# PotsDuino.net
KiCad netlist of a schematic drawn in Altium Designer
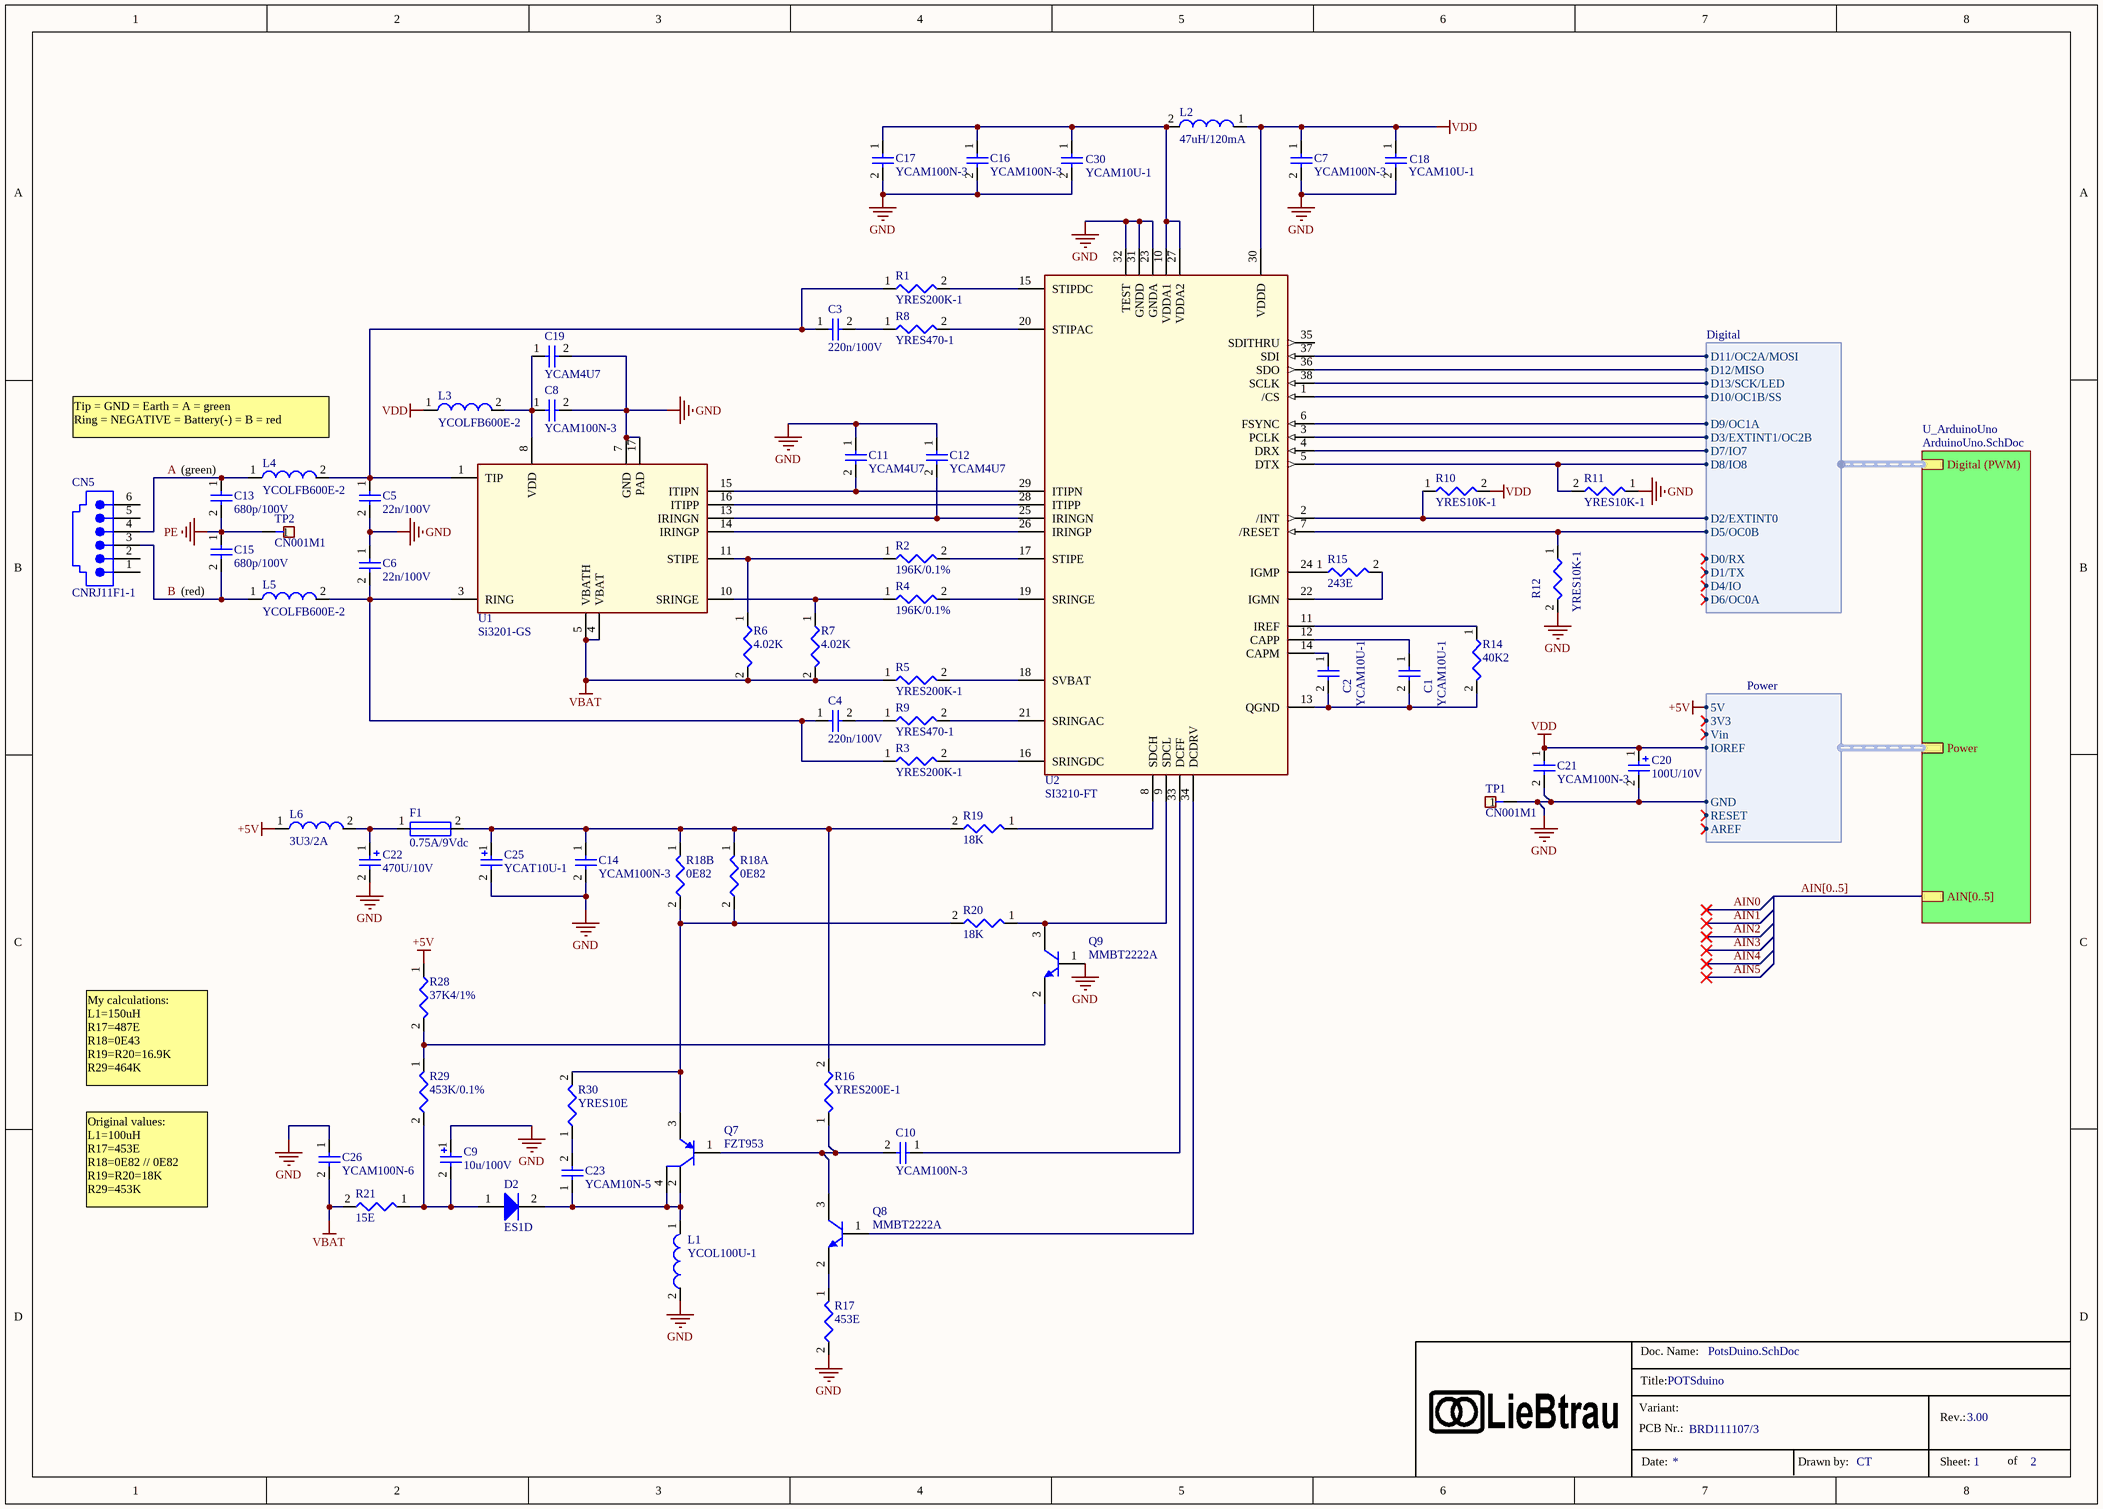
[diagram p0: PotsDuino.SchDoc]

(export (version "E")
  (design (tool "Eeschema 10.0.6"))
  (components
    (comp (ref "C1") (value "YCAM10U-1") (footprint "CA_0805") (libsource (lib "Testing") (part "CA_NONPOL")))
    (comp (ref "C2") (value "YCAM10U-1") (footprint "CA_0805") (libsource (lib "Testing") (part "CA_NONPOL")))
    (comp (ref "C3")
      (value "220n/100V")
      (footprint "CA_0805")
      (fields (field (name "PART NUMBER") "MCCA000493") (field (name "MANUFACTURER") "Multicomp"))
      (libsource (lib "Testing") (part "CA_NONPOL"))
    )
    (comp (ref "C4")
      (value "220n/100V")
      (footprint "CA_0805")
      (fields (field (name "PART NUMBER") "MCCA000493") (field (name "MANUFACTURER") "Multicomp"))
      (libsource (lib "Testing") (part "CA_NONPOL"))
    )
    (comp (ref "C5")
      (value "22n/100V")
      (footprint "CA_0603")
      (fields (field (name "PART NUMBER") "C0603C223K1RACTU") (field (name "MANUFACTURER") "Kemet"))
      (libsource (lib "Testing") (part "CA_NONPOL"))
    )
    (comp (ref "C6")
      (value "22n/100V")
      (footprint "CA_0603")
      (fields (field (name "PART NUMBER") "C0603C223K1RACTU") (field (name "MANUFACTURER") "Kemet"))
      (libsource (lib "Testing") (part "CA_NONPOL"))
    )
    (comp (ref "C7")
      (value "YCAM100N-3")
      (footprint "CA_0603")
      (libsource (lib "Testing") (part "CA_NONPOL"))
    )
    (comp (ref "C8")
      (value "YCAM100N-3")
      (footprint "CA_0603")
      (libsource (lib "Testing") (part "CA_NONPOL"))
    )
    (comp (ref "C9")
      (value "10u/100V")
      (footprint "CA_CANTHD63P25_H110_R")
      (fields (field (name "PART NUMBER") "100YXF10MEFC6.3X11") (field (name "MANUFACTURER") "Rubycon"))
      (libsource (lib "Testing") (part "CA_POL"))
    )
    (comp (ref "C10")
      (value "YCAM100N-3")
      (footprint "CA_0603")
      (libsource (lib "Testing") (part "CA_NONPOL"))
    )
    (comp (ref "C11") (value "YCAM4U7") (footprint "CA_1206") (libsource (lib "Testing") (part "CA_NONPOL")))
    (comp (ref "C12") (value "YCAM4U7") (footprint "CA_1206") (libsource (lib "Testing") (part "CA_NONPOL")))
    (comp (ref "C13")
      (value "680p/100V")
      (footprint "CA_0603")
      (fields (field (name "PART NUMBER") "C0603C681J1GACTU") (field (name "MANUFACTURER") "Kemet"))
      (libsource (lib "Testing") (part "CA_NONPOL"))
    )
    (comp (ref "C14")
      (value "YCAM100N-3")
      (footprint "CA_0603")
      (libsource (lib "Testing") (part "CA_NONPOL"))
    )
    (comp (ref "C15")
      (value "680p/100V")
      (footprint "CA_0603")
      (fields (field (name "PART NUMBER") "C0603C681J1GACTU") (field (name "MANUFACTURER") "Kemet"))
      (libsource (lib "Testing") (part "CA_NONPOL"))
    )
    (comp (ref "C16")
      (value "YCAM100N-3")
      (footprint "CA_0603")
      (libsource (lib "Testing") (part "CA_NONPOL"))
    )
    (comp (ref "C17")
      (value "YCAM100N-3")
      (footprint "CA_0603")
      (libsource (lib "Testing") (part "CA_NONPOL"))
    )
    (comp (ref "C18")
      (value "YCAM10U-1")
      (footprint "CA_0805")
      (libsource (lib "Testing") (part "CA_NONPOL"))
    )
    (comp (ref "C19") (value "YCAM4U7") (footprint "CA_1206") (libsource (lib "Testing") (part "CA_NONPOL")))
    (comp (ref "C20")
      (value "100U/10V")
      (footprint "CA_CANTHD50P20_H110")
      (fields (field (name "PART NUMBER") "MCGPR10V107M5X11") (field (name "MANUFACTURER") "Multicomp"))
      (libsource (lib "Testing") (part "CA_POL"))
    )
    (comp (ref "C21")
      (value "YCAM100N-3")
      (footprint "CA_0603")
      (libsource (lib "Testing") (part "CA_NONPOL"))
    )
    (comp (ref "C22")
      (value "470U/10V")
      (footprint "CA_CANTHD80P35_H110")
      (fields (field (name "PART NUMBER") "MCGPR10V477M8X11") (field (name "MANUFACTURER") "Multicomp"))
      (libsource (lib "Testing") (part "CA_POL"))
    )
    (comp (ref "C23")
      (value "YCAM10N-5")
      (footprint "CA_1206")
      (fields (field (name "MANUFACTURER") "Yageo (Phycomp)"))
      (libsource (lib "Testing") (part "CA_NONPOL"))
    )
    (comp (ref "C25")
      (value "YCAT10U-1")
      (footprint "CA_1210_H21")
      (libsource (lib "Testing") (part "CA_POL"))
    )
    (comp (ref "C26")
      (value "YCAM100N-6")
      (footprint "CA_0805")
      (libsource (lib "Testing") (part "CA_NONPOL"))
    )
    (comp (ref "C30")
      (value "YCAM10U-1")
      (footprint "CA_0805")
      (libsource (lib "Testing") (part "CA_NONPOL"))
    )
    (comp (ref "CN5")
      (value "CNRJ11F1-1")
      (footprint "CN_MODJACK_6P")
      (libsource (lib "Testing") (part "CN_MODJACK_6P"))
    )
    (comp (ref "D2")
      (value "ES1D")
      (footprint "DI_DO-214AC")
      (description "1 Amp General Purpose Rectifier")
      (fields (field (name "MANUFACTURER") "Fairchild Semiconductor"))
      (libsource (lib "Testing") (part "DI_DIODE"))
    )
    (comp (ref "F1")
      (value "0.75A/9Vdc")
      (footprint "RE_0805")
      (fields (field (name "PART NUMBER") "MC36210") (field (name "MANUFACTURER") "Multicomp"))
      (libsource (lib "Testing") (part "FU_FUSE"))
    )
    (comp (ref "L1")
      (value "YCOL100U-1")
      (footprint "CL_WE-PD4")
      (fields (field (name "MANUFACTURER") "Wuerth Elektronik"))
      (libsource (lib "") (part "CL_COIL_1"))
    )
    (comp (ref "L2")
      (value "47uH/120mA")
      (footprint "CL_0805")
      (fields (field (name "PART NUMBER") "L0805C470MDWIT") (field (name "MANUFACTURER") "Kemet"))
      (libsource (lib "") (part "CL_COIL_1"))
    )
    (comp (ref "L3")
      (value "YCOLFB600E-2")
      (footprint "CL_0603")
      (fields (field (name "MANUFACTURER") "Murata"))
      (libsource (lib "Testing") (part "CL_COIL"))
    )
    (comp (ref "L4")
      (value "YCOLFB600E-2")
      (footprint "CL_0603")
      (fields (field (name "MANUFACTURER") "Murata"))
      (libsource (lib "Testing") (part "CL_COIL"))
    )
    (comp (ref "L5")
      (value "YCOLFB600E-2")
      (footprint "CL_0603")
      (fields (field (name "MANUFACTURER") "Murata"))
      (libsource (lib "Testing") (part "CL_COIL"))
    )
    (comp (ref "L6")
      (value "3U3/2A")
      (footprint "CL_BOURNS_SDR0604_58x60")
      (fields (field (name "PART NUMBER") "MCSDC0604-3R3MU") (field (name "MANUFACTURER") "Multicomp"))
      (libsource (lib "Testing") (part "CL_COIL"))
    )
    (comp (ref "Q7")
      (value "FZT953")
      (footprint "SC_SOT223")
      (description "Amplifier Transistor NPN Silicon")
      (fields (field (name "MANUFACTURER") "Diodes Inc."))
      (libsource (lib "Testing") (part "TR_PNP_1"))
    )
    (comp (ref "Q8")
      (value "MMBT2222A")
      (footprint "SC_SOT23")
      (description "Amplifier Transistor NPN Silicon")
      (fields (field (name "MANUFACTURER") "Fairchild Semiconductor"))
      (libsource (lib "Testing") (part "TR_NPN_1"))
    )
    (comp (ref "Q9")
      (value "MMBT2222A")
      (footprint "SC_SOT23")
      (description "Amplifier Transistor NPN Silicon")
      (fields (field (name "MANUFACTURER") "Fairchild Semiconductor"))
      (libsource (lib "Testing") (part "TR_NPN_1"))
    )
    (comp (ref "R1")
      (value "YRES200K-1")
      (footprint "RE_0603")
      (description "Resistor")
      (libsource (lib "Testing") (part "RE_RES"))
    )
    (comp (ref "R2")
      (value "196K/0.1%")
      (footprint "RE_0603")
      (description "Resistor")
      (fields
        (field (name "PART NUMBER") "ERA3AEB1963V")
        (field (name "MANUFACTURER") "Panasonic Electronic Components")
      )
      (libsource (lib "Testing") (part "RE_RES"))
    )
    (comp (ref "R3")
      (value "YRES200K-1")
      (footprint "RE_0603")
      (description "Resistor")
      (libsource (lib "Testing") (part "RE_RES"))
    )
    (comp (ref "R4")
      (value "196K/0.1%")
      (footprint "RE_0603")
      (description "Resistor")
      (fields
        (field (name "PART NUMBER") "ERA3AEB1963V")
        (field (name "MANUFACTURER") "Panasonic Electronic Components")
      )
      (libsource (lib "Testing") (part "RE_RES"))
    )
    (comp (ref "R5")
      (value "YRES200K-1")
      (footprint "RE_0603")
      (description "Resistor")
      (libsource (lib "Testing") (part "RE_RES"))
    )
    (comp (ref "R6")
      (value "4.02K")
      (footprint "RE_1206")
      (description "Resistor")
      (fields (field (name "PART NUMBER") "CRCW12064K02FKEA") (field (name "MANUFACTURER") "Vishay Draloric"))
      (libsource (lib "Testing") (part "RE_RES"))
    )
    (comp (ref "R7")
      (value "4.02K")
      (footprint "RE_1206")
      (description "Resistor")
      (fields (field (name "PART NUMBER") "CRCW12064K02FKEA") (field (name "MANUFACTURER") "Vishay Draloric"))
      (libsource (lib "Testing") (part "RE_RES"))
    )
    (comp (ref "R8")
      (value "YRES470-1")
      (footprint "RE_0603")
      (description "Resistor")
      (libsource (lib "Testing") (part "RE_RES"))
    )
    (comp (ref "R9")
      (value "YRES470-1")
      (footprint "RE_0603")
      (description "Resistor")
      (libsource (lib "Testing") (part "RE_RES"))
    )
    (comp (ref "R10")
      (value "YRES10K-1")
      (footprint "RE_0603")
      (description "Resistor")
      (libsource (lib "Testing") (part "RE_RES"))
    )
    (comp (ref "R11")
      (value "YRES10K-1")
      (footprint "RE_0603")
      (description "Resistor")
      (libsource (lib "Testing") (part "RE_RES"))
    )
    (comp (ref "R12")
      (value "YRES10K-1")
      (footprint "RE_0603")
      (description "Resistor")
      (libsource (lib "Testing") (part "RE_RES"))
    )
    (comp (ref "R14")
      (value "40K2")
      (footprint "RE_0603")
      (description "Resistor")
      (fields (field (name "PART NUMBER") "MC 0.063W 0603 1% 40K2") (field (name "MANUFACTURER") "Multicomp"))
      (libsource (lib "Testing") (part "RE_RES"))
    )
    (comp (ref "R15")
      (value "243E")
      (footprint "RE_0603")
      (description "Resistor")
      (fields (field (name "PART NUMBER") "MC 0.063W 0603 1% 243R") (field (name "MANUFACTURER") "Multicomp"))
      (libsource (lib "Testing") (part "RE_RES"))
    )
    (comp (ref "R16")
      (value "YRES200E-1")
      (footprint "RE_0603")
      (description "Resistor")
      (libsource (lib "Testing") (part "RE_RES"))
    )
    (comp (ref "R17")
      (value "453E")
      (footprint "RE_0805")
      (description "Resistor")
      (fields (field (name "PART NUMBER") "MCTC0525B4530T5E") (field (name "MANUFACTURER") "Multicomp"))
      (libsource (lib "Testing") (part "RE_RES"))
    )
    (comp (ref "R18A")
      (value "0E82")
      (footprint "RE_0805")
      (description "Resistor")
      (fields
        (field (name "PART NUMBER") "ERJ6RQFR82V")
        (field (name "MANUFACTURER") "Panasonic Electronic Components")
      )
      (libsource (lib "Testing") (part "RE_RES"))
    )
    (comp (ref "R18B")
      (value "0E82")
      (footprint "RE_0805")
      (description "Resistor")
      (fields
        (field (name "PART NUMBER") "ERJ6RQFR82V")
        (field (name "MANUFACTURER") "Panasonic Electronic Components")
      )
      (libsource (lib "Testing") (part "RE_RES"))
    )
    (comp (ref "R19")
      (value "18K")
      (footprint "RE_0603")
      (description "Resistor")
      (fields (field (name "PART NUMBER") "SG73S1JTTD1802F") (field (name "MANUFACTURER") "KOA"))
      (libsource (lib "Testing") (part "RE_RES"))
    )
    (comp (ref "R20")
      (value "18K")
      (footprint "RE_0603")
      (description "Resistor")
      (fields (field (name "PART NUMBER") "SG73S1JTTD1802F") (field (name "MANUFACTURER") "KOA"))
      (libsource (lib "Testing") (part "RE_RES"))
    )
    (comp (ref "R21")
      (value "15E")
      (footprint "RE_0805")
      (description "Resistor")
      (fields (field (name "PART NUMBER") "SG73P2ATTD15R0F") (field (name "MANUFACTURER") "KOA"))
      (libsource (lib "Testing") (part "RE_RES"))
    )
    (comp (ref "R28")
      (value "37K4/1%")
      (footprint "RE_1206")
      (description "Resistor")
      (fields (field (name "PART NUMBER") "CRCW120637K4FKEA") (field (name "MANUFACTURER") "Vishay Draloric"))
      (libsource (lib "Testing") (part "RE_RES"))
    )
    (comp (ref "R29")
      (value "453K/0.1%")
      (footprint "RE_0805")
      (description "Resistor")
      (fields (field (name "PART NUMBER") "MCTC0525B4533T5E") (field (name "MANUFACTURER") "Multicomp"))
      (libsource (lib "Testing") (part "RE_RES"))
    )
    (comp (ref "R30")
      (value "YRES10E")
      (footprint "RE_1206")
      (description "Resistor")
      (fields (field (name "MANUFACTURER") "Vishay Draloric"))
      (libsource (lib "Testing") (part "RE_RES"))
    )
    (comp (ref "TP1")
      (value "CN001M1")
      (footprint "CN_TP_TH_1.3mm")
      (libsource (lib "") (part "CN_TESTPIN_1"))
    )
    (comp (ref "TP2")
      (value "CN001M1")
      (footprint "CN_TP_TH_1.3mm")
      (libsource (lib "Testing") (part "CN_TESTPIN"))
    )
    (comp (ref "U1")
      (value "Si3201-GS")
      (footprint "SC_ESOIC16")
      (fields (field (name "MANUFACTURER") "Silicon Labs"))
      (libsource (lib "Testing") (part "IC_Si3201"))
    )
    (comp (ref "U2")
      (value "SI3210-FT")
      (footprint "SC_TSSOP38")
      (fields (field (name "MANUFACTURER") "Silicon Labs"))
      (libsource (lib "Testing") (part "IC_Si3210"))
    )
  )
  (nets
    (net (code "3") (name "+5V") (class "Default")
      (node (ref "L6") (pin "1") (pinfunction "1_1") (pintype "passive"))
      (node (ref "R28") (pin "1") (pinfunction "1_1") (pintype "passive"))
    )
    (net (code "4") (name "/A") (class "Default")
      (node (ref "C13") (pin "1") (pinfunction "1_1") (pintype "passive"))
      (node (ref "CN5") (pin "4") (pinfunction "4_4") (pintype "passive"))
      (node (ref "L4") (pin "1") (pinfunction "1_1") (pintype "passive"))
    )
    (net (code "12") (name "/B") (class "Default")
      (node (ref "C15") (pin "2") (pinfunction "2_2") (pintype "passive"))
      (node (ref "CN5") (pin "3") (pinfunction "3_3") (pintype "passive"))
      (node (ref "L5") (pin "1") (pinfunction "1_1") (pintype "passive"))
    )
    (net (code "13") (name "/D2{slash}EXTINT0") (class "Default")
      (node (ref "R10") (pin "1") (pinfunction "1_1") (pintype "passive"))
      (node (ref "U2") (pin "2") (pinfunction "/INT_2") (pintype "output"))
    )
    (net (code "14") (name "/D3{slash}EXTINT1{slash}OC2B") (class "Default")
      (node (ref "U2") (pin "3") (pinfunction "PCLK_3") (pintype "input"))
    )
    (net (code "15") (name "/D5{slash}OC0B") (class "Default")
      (node (ref "R12") (pin "1") (pinfunction "1_1") (pintype "passive"))
      (node (ref "U2") (pin "7") (pinfunction "/RESET_7") (pintype "input"))
    )
    (net (code "16") (name "/D7{slash}IO7") (class "Default")
      (node (ref "U2") (pin "4") (pinfunction "DRX_4") (pintype "input"))
    )
    (net (code "17") (name "/D8{slash}IO8") (class "Default")
      (node (ref "R11") (pin "2") (pinfunction "2_2") (pintype "passive"))
      (node (ref "U2") (pin "5") (pinfunction "DTX_5") (pintype "output"))
    )
    (net (code "18") (name "/D9{slash}OC1A") (class "Default")
      (node (ref "U2") (pin "6") (pinfunction "FSYNC_6") (pintype "input"))
    )
    (net (code "19") (name "/D10{slash}OC1B{slash}SS") (class "Default")
      (node (ref "U2") (pin "1") (pinfunction "/CS_1") (pintype "input"))
    )
    (net (code "20") (name "/D11{slash}OC2A{slash}MOSI") (class "Default")
      (node (ref "U2") (pin "37") (pinfunction "SDI_37") (pintype "input"))
    )
    (net (code "21") (name "/D12{slash}MISO") (class "Default")
      (node (ref "U2") (pin "36") (pinfunction "SDO_36") (pintype "output"))
    )
    (net (code "22") (name "/D13{slash}SCK{slash}LED") (class "Default")
      (node (ref "U2") (pin "38") (pinfunction "SCLK_38") (pintype "input"))
    )
    (net (code "25") (name "GND") (class "Default")
      (node (ref "C11") (pin "1") (pinfunction "1_1") (pintype "passive"))
      (node (ref "C12") (pin "1") (pinfunction "1_1") (pintype "passive"))
      (node (ref "C14") (pin "2") (pinfunction "2_2") (pintype "passive"))
      (node (ref "C16") (pin "2") (pinfunction "2_2") (pintype "passive"))
      (node (ref "C17") (pin "2") (pinfunction "2_2") (pintype "passive"))
      (node (ref "C18") (pin "2") (pinfunction "2_2") (pintype "passive"))
      (node (ref "C19") (pin "2") (pinfunction "2_2") (pintype "passive"))
      (node (ref "C20") (pin "2") (pinfunction "2_2") (pintype "passive"))
      (node (ref "C21") (pin "2") (pinfunction "2_2") (pintype "passive"))
      (node (ref "C22") (pin "2") (pinfunction "2_2") (pintype "passive"))
      (node (ref "C25") (pin "2") (pinfunction "2_2") (pintype "passive"))
      (node (ref "C26") (pin "1") (pinfunction "1_1") (pintype "passive"))
      (node (ref "C30") (pin "2") (pinfunction "2_2") (pintype "passive"))
      (node (ref "C5") (pin "2") (pinfunction "2_2") (pintype "passive"))
      (node (ref "C6") (pin "1") (pinfunction "1_1") (pintype "passive"))
      (node (ref "C7") (pin "2") (pinfunction "2_2") (pintype "passive"))
      (node (ref "C8") (pin "2") (pinfunction "2_2") (pintype "passive"))
      (node (ref "C9") (pin "1") (pinfunction "1_1") (pintype "passive"))
      (node (ref "L1") (pin "2") (pinfunction "2_2") (pintype "passive"))
      (node (ref "Q9") (pin "1") (pinfunction "C_1") (pintype "passive"))
      (node (ref "R11") (pin "1") (pinfunction "1_1") (pintype "passive"))
      (node (ref "R12") (pin "2") (pinfunction "2_2") (pintype "passive"))
      (node (ref "R17") (pin "2") (pinfunction "2_2") (pintype "passive"))
      (node (ref "TP1") (pin "1") (pinfunction "1_1") (pintype "passive"))
      (node (ref "U1") (pin "17") (pinfunction "PAD_17") (pintype "passive"))
      (node (ref "U1") (pin "7") (pinfunction "GND_7") (pintype "passive"))
      (node (ref "U2") (pin "23") (pinfunction "GNDA_23") (pintype "passive"))
      (node (ref "U2") (pin "31") (pinfunction "GNDD_31") (pintype "passive"))
      (node (ref "U2") (pin "32") (pinfunction "TEST_32") (pintype "passive"))
    )
    (net (code "26") (name "Net-(C3-Pad2)") (class "Default")
      (node (ref "C3") (pin "2") (pinfunction "2_2") (pintype "passive"))
      (node (ref "R8") (pin "1") (pinfunction "1_1") (pintype "passive"))
    )
    (net (code "27") (name "Net-(C4-Pad2)") (class "Default")
      (node (ref "C4") (pin "2") (pinfunction "2_2") (pintype "passive"))
      (node (ref "R9") (pin "1") (pinfunction "1_1") (pintype "passive"))
    )
    (net (code "28") (name "Net-(C14-Pad1)") (class "Default")
      (node (ref "C14") (pin "1") (pinfunction "1_1") (pintype "passive"))
      (node (ref "C25") (pin "1") (pinfunction "1_1") (pintype "passive"))
      (node (ref "F1") (pin "2") (pinfunction "2_2") (pintype "passive"))
      (node (ref "R16") (pin "2") (pinfunction "2_2") (pintype "passive"))
      (node (ref "R18A") (pin "1") (pinfunction "1_1") (pintype "passive"))
      (node (ref "R18B") (pin "1") (pinfunction "1_1") (pintype "passive"))
      (node (ref "R19") (pin "2") (pinfunction "2_2") (pintype "passive"))
    )
    (net (code "29") (name "Net-(C22-Pad1)") (class "Default")
      (node (ref "C22") (pin "1") (pinfunction "1_1") (pintype "passive"))
      (node (ref "F1") (pin "1") (pinfunction "1_1") (pintype "passive"))
      (node (ref "L6") (pin "2") (pinfunction "2_2") (pintype "passive"))
    )
    (net (code "30") (name "Net-(C23-Pad2)") (class "Default")
      (node (ref "C23") (pin "2") (pinfunction "2_2") (pintype "passive"))
      (node (ref "R30") (pin "1") (pinfunction "1_1") (pintype "passive"))
    )
    (net (code "31") (name "Net-(D2-A)") (class "Default")
      (node (ref "C9") (pin "2") (pinfunction "2_2") (pintype "passive"))
      (node (ref "D2") (pin "1") (pinfunction "A_1") (pintype "passive"))
      (node (ref "R21") (pin "1") (pinfunction "1_1") (pintype "passive"))
      (node (ref "R29") (pin "2") (pinfunction "2_2") (pintype "passive"))
    )
    (net (code "32") (name "Net-(D2-K)") (class "Default")
      (node (ref "C23") (pin "1") (pinfunction "1_1") (pintype "passive"))
      (node (ref "D2") (pin "2") (pinfunction "K_2") (pintype "passive"))
      (node (ref "L1") (pin "1") (pinfunction "1_1") (pintype "passive"))
      (node (ref "Q7") (pin "2") (pinfunction "B_2") (pintype "passive"))
      (node (ref "Q7") (pin "4") (pinfunction "4_4") (pintype "passive"))
    )
    (net (code "33") (name "Net-(Q7-C)") (class "Default")
      (node (ref "C10") (pin "2") (pinfunction "2_2") (pintype "passive"))
      (node (ref "Q7") (pin "1") (pinfunction "C_1") (pintype "passive"))
      (node (ref "Q8") (pin "3") (pinfunction "E_3") (pintype "passive"))
      (node (ref "R16") (pin "1") (pinfunction "1_1") (pintype "passive"))
    )
    (net (code "34") (name "Net-(Q7-E)") (class "Default")
      (node (ref "Q7") (pin "3") (pinfunction "E_3") (pintype "passive"))
      (node (ref "R18A") (pin "2") (pinfunction "2_2") (pintype "passive"))
      (node (ref "R18B") (pin "2") (pinfunction "2_2") (pintype "passive"))
      (node (ref "R20") (pin "2") (pinfunction "2_2") (pintype "passive"))
      (node (ref "R30") (pin "2") (pinfunction "2_2") (pintype "passive"))
    )
    (net (code "35") (name "Net-(Q8-B)") (class "Default")
      (node (ref "Q8") (pin "2") (pinfunction "B_2") (pintype "passive"))
      (node (ref "R17") (pin "1") (pinfunction "1_1") (pintype "passive"))
    )
    (net (code "36") (name "Net-(Q8-C)") (class "Default")
      (node (ref "Q8") (pin "1") (pinfunction "C_1") (pintype "passive"))
      (node (ref "U2") (pin "34") (pinfunction "DCDRV_34") (pintype "passive"))
    )
    (net (code "37") (name "Net-(Q9-B)") (class "Default")
      (node (ref "Q9") (pin "2") (pinfunction "B_2") (pintype "passive"))
      (node (ref "R28") (pin "2") (pinfunction "2_2") (pintype "passive"))
      (node (ref "R29") (pin "1") (pinfunction "1_1") (pintype "passive"))
    )
    (net (code "38") (name "Net-(Q9-E)") (class "Default")
      (node (ref "Q9") (pin "3") (pinfunction "E_3") (pintype "passive"))
      (node (ref "R20") (pin "1") (pinfunction "1_1") (pintype "passive"))
      (node (ref "U2") (pin "9") (pinfunction "SDCL_9") (pintype "passive"))
    )
    (net (code "39") (name "Net-(U1-IRINGN)") (class "Default")
      (node (ref "C12") (pin "2") (pinfunction "2_2") (pintype "passive"))
      (node (ref "U1") (pin "13") (pinfunction "IRINGN_13") (pintype "passive"))
      (node (ref "U2") (pin "25") (pinfunction "IRINGN_25") (pintype "passive"))
    )
    (net (code "40") (name "Net-(U1-IRINGP)") (class "Default")
      (node (ref "U1") (pin "14") (pinfunction "IRINGP_14") (pintype "passive"))
      (node (ref "U2") (pin "26") (pinfunction "IRINGP_26") (pintype "passive"))
    )
    (net (code "41") (name "Net-(U1-ITIPN)") (class "Default")
      (node (ref "C11") (pin "2") (pinfunction "2_2") (pintype "passive"))
      (node (ref "U1") (pin "15") (pinfunction "ITIPN_15") (pintype "passive"))
      (node (ref "U2") (pin "29") (pinfunction "ITIPN_29") (pintype "passive"))
    )
    (net (code "42") (name "Net-(U1-ITIPP)") (class "Default")
      (node (ref "U1") (pin "16") (pinfunction "ITIPP_16") (pintype "passive"))
      (node (ref "U2") (pin "28") (pinfunction "ITIPP_28") (pintype "passive"))
    )
    (net (code "43") (name "Net-(U1-RING)") (class "Default")
      (node (ref "C4") (pin "1") (pinfunction "1_1") (pintype "passive"))
      (node (ref "C6") (pin "2") (pinfunction "2_2") (pintype "passive"))
      (node (ref "L5") (pin "2") (pinfunction "2_2") (pintype "passive"))
      (node (ref "R3") (pin "1") (pinfunction "1_1") (pintype "passive"))
      (node (ref "U1") (pin "3") (pinfunction "RING_3") (pintype "passive"))
    )
    (net (code "44") (name "Net-(U1-SRINGE)") (class "Default")
      (node (ref "R4") (pin "1") (pinfunction "1_1") (pintype "passive"))
      (node (ref "R7") (pin "1") (pinfunction "1_1") (pintype "passive"))
      (node (ref "U1") (pin "10") (pinfunction "SRINGE_10") (pintype "passive"))
    )
    (net (code "45") (name "Net-(U1-STIPE)") (class "Default")
      (node (ref "R2") (pin "1") (pinfunction "1_1") (pintype "passive"))
      (node (ref "R6") (pin "1") (pinfunction "1_1") (pintype "passive"))
      (node (ref "U1") (pin "11") (pinfunction "STIPE_11") (pintype "passive"))
    )
    (net (code "46") (name "Net-(U1-TIP)") (class "Default")
      (node (ref "C3") (pin "1") (pinfunction "1_1") (pintype "passive"))
      (node (ref "C5") (pin "1") (pinfunction "1_1") (pintype "passive"))
      (node (ref "L4") (pin "2") (pinfunction "2_2") (pintype "passive"))
      (node (ref "R1") (pin "1") (pinfunction "1_1") (pintype "passive"))
      (node (ref "U1") (pin "1") (pinfunction "TIP_1") (pintype "passive"))
    )
    (net (code "47") (name "Net-(U1-VDD)") (class "Default")
      (node (ref "C19") (pin "1") (pinfunction "1_1") (pintype "passive"))
      (node (ref "C8") (pin "1") (pinfunction "1_1") (pintype "passive"))
      (node (ref "L3") (pin "2") (pinfunction "2_2") (pintype "passive"))
      (node (ref "U1") (pin "8") (pinfunction "VDD_8") (pintype "passive"))
    )
    (net (code "48") (name "Net-(U2-CAPM)") (class "Default")
      (node (ref "C2") (pin "1") (pinfunction "1_1") (pintype "passive"))
      (node (ref "U2") (pin "14") (pinfunction "CAPM_14") (pintype "passive"))
    )
    (net (code "49") (name "Net-(U2-CAPP)") (class "Default")
      (node (ref "C1") (pin "1") (pinfunction "1_1") (pintype "passive"))
      (node (ref "U2") (pin "12") (pinfunction "CAPP_12") (pintype "passive"))
    )
    (net (code "50") (name "Net-(U2-DCFF)") (class "Default")
      (node (ref "C10") (pin "1") (pinfunction "1_1") (pintype "passive"))
      (node (ref "U2") (pin "33") (pinfunction "DCFF_33") (pintype "passive"))
    )
    (net (code "51") (name "Net-(U2-IGMN)") (class "Default")
      (node (ref "R15") (pin "2") (pinfunction "2_2") (pintype "passive"))
      (node (ref "U2") (pin "22") (pinfunction "IGMN_22") (pintype "passive"))
    )
    (net (code "52") (name "Net-(U2-IGMP)") (class "Default")
      (node (ref "R15") (pin "1") (pinfunction "1_1") (pintype "passive"))
      (node (ref "U2") (pin "24") (pinfunction "IGMP_24") (pintype "passive"))
    )
    (net (code "53") (name "Net-(U2-IREF)") (class "Default")
      (node (ref "R14") (pin "1") (pinfunction "1_1") (pintype "passive"))
      (node (ref "U2") (pin "11") (pinfunction "IREF_11") (pintype "passive"))
    )
    (net (code "54") (name "Net-(U2-QGND)") (class "Default")
      (node (ref "C1") (pin "2") (pinfunction "2_2") (pintype "passive"))
      (node (ref "C2") (pin "2") (pinfunction "2_2") (pintype "passive"))
      (node (ref "R14") (pin "2") (pinfunction "2_2") (pintype "passive"))
      (node (ref "U2") (pin "13") (pinfunction "QGND_13") (pintype "passive"))
    )
    (net (code "55") (name "Net-(U2-SDCH)") (class "Default")
      (node (ref "R19") (pin "1") (pinfunction "1_1") (pintype "passive"))
      (node (ref "U2") (pin "8") (pinfunction "SDCH_8") (pintype "passive"))
    )
    (net (code "56") (name "Net-(U2-SRINGAC)") (class "Default")
      (node (ref "R9") (pin "2") (pinfunction "2_2") (pintype "passive"))
      (node (ref "U2") (pin "21") (pinfunction "SRINGAC_21") (pintype "passive"))
    )
    (net (code "57") (name "Net-(U2-SRINGDC)") (class "Default")
      (node (ref "R3") (pin "2") (pinfunction "2_2") (pintype "passive"))
      (node (ref "U2") (pin "16") (pinfunction "SRINGDC_16") (pintype "passive"))
    )
    (net (code "58") (name "Net-(U2-SRINGE)") (class "Default")
      (node (ref "R4") (pin "2") (pinfunction "2_2") (pintype "passive"))
      (node (ref "U2") (pin "19") (pinfunction "SRINGE_19") (pintype "passive"))
    )
    (net (code "59") (name "Net-(U2-STIPAC)") (class "Default")
      (node (ref "R8") (pin "2") (pinfunction "2_2") (pintype "passive"))
      (node (ref "U2") (pin "20") (pinfunction "STIPAC_20") (pintype "passive"))
    )
    (net (code "60") (name "Net-(U2-STIPDC)") (class "Default")
      (node (ref "R1") (pin "2") (pinfunction "2_2") (pintype "passive"))
      (node (ref "U2") (pin "15") (pinfunction "STIPDC_15") (pintype "passive"))
    )
    (net (code "61") (name "Net-(U2-STIPE)") (class "Default")
      (node (ref "R2") (pin "2") (pinfunction "2_2") (pintype "passive"))
      (node (ref "U2") (pin "17") (pinfunction "STIPE_17") (pintype "passive"))
    )
    (net (code "62") (name "Net-(U2-SVBAT)") (class "Default")
      (node (ref "R5") (pin "2") (pinfunction "2_2") (pintype "passive"))
      (node (ref "U2") (pin "18") (pinfunction "SVBAT_18") (pintype "passive"))
    )
    (net (code "63") (name "Net-(U2-VDDA1)") (class "Default")
      (node (ref "C16") (pin "1") (pinfunction "1_1") (pintype "passive"))
      (node (ref "C17") (pin "1") (pinfunction "1_1") (pintype "passive"))
      (node (ref "C30") (pin "1") (pinfunction "1_1") (pintype "passive"))
      (node (ref "L2") (pin "2") (pinfunction "2_2") (pintype "passive"))
      (node (ref "U2") (pin "10") (pinfunction "VDDA1_10") (pintype "passive"))
      (node (ref "U2") (pin "27") (pinfunction "VDDA2_27") (pintype "passive"))
    )
    (net (code "64") (name "PE") (class "Default")
      (node (ref "C13") (pin "2") (pinfunction "2_2") (pintype "passive"))
      (node (ref "C15") (pin "1") (pinfunction "1_1") (pintype "passive"))
      (node (ref "TP2") (pin "1") (pinfunction "1_1") (pintype "passive"))
    )
    (net (code "65") (name "VBAT") (class "Default")
      (node (ref "C26") (pin "2") (pinfunction "2_2") (pintype "passive"))
      (node (ref "R21") (pin "2") (pinfunction "2_2") (pintype "passive"))
      (node (ref "R5") (pin "1") (pinfunction "1_1") (pintype "passive"))
      (node (ref "R6") (pin "2") (pinfunction "2_2") (pintype "passive"))
      (node (ref "R7") (pin "2") (pinfunction "2_2") (pintype "passive"))
      (node (ref "U1") (pin "4") (pinfunction "VBAT_4") (pintype "passive"))
      (node (ref "U1") (pin "5") (pinfunction "VBATH_5") (pintype "passive"))
    )
    (net (code "66") (name "VDD") (class "Default")
      (node (ref "C18") (pin "1") (pinfunction "1_1") (pintype "passive"))
      (node (ref "C20") (pin "1") (pinfunction "1_1") (pintype "passive"))
      (node (ref "C21") (pin "1") (pinfunction "1_1") (pintype "passive"))
      (node (ref "C7") (pin "1") (pinfunction "1_1") (pintype "passive"))
      (node (ref "L2") (pin "1") (pinfunction "1_1") (pintype "passive"))
      (node (ref "L3") (pin "1") (pinfunction "1_1") (pintype "passive"))
      (node (ref "R10") (pin "2") (pinfunction "2_2") (pintype "passive"))
      (node (ref "U2") (pin "30") (pinfunction "VDDD_30") (pintype "passive"))
    )
    (net (code "67") (name "unconnected-(CN5-Pad1)") (class "Default")
      (node (ref "CN5") (pin "1") (pinfunction "1_1") (pintype "passive"))
    )
    (net (code "68") (name "unconnected-(CN5-Pad2)") (class "Default")
      (node (ref "CN5") (pin "2") (pinfunction "2_2") (pintype "passive"))
    )
    (net (code "69") (name "unconnected-(CN5-Pad5)") (class "Default")
      (node (ref "CN5") (pin "5") (pinfunction "5_5") (pintype "passive"))
    )
    (net (code "70") (name "unconnected-(CN5-Pad6)") (class "Default")
      (node (ref "CN5") (pin "6") (pinfunction "6_6") (pintype "passive"))
    )
    (net (code "71") (name "unconnected-(U2-SDITHRU-Pad35)") (class "Default")
      (node (ref "U2") (pin "35") (pinfunction "SDITHRU_35") (pintype "output"))
    )
  )
)
